# demeter_v28-TSSOP.net
KiCad netlist of a schematic drawn in EAGLE
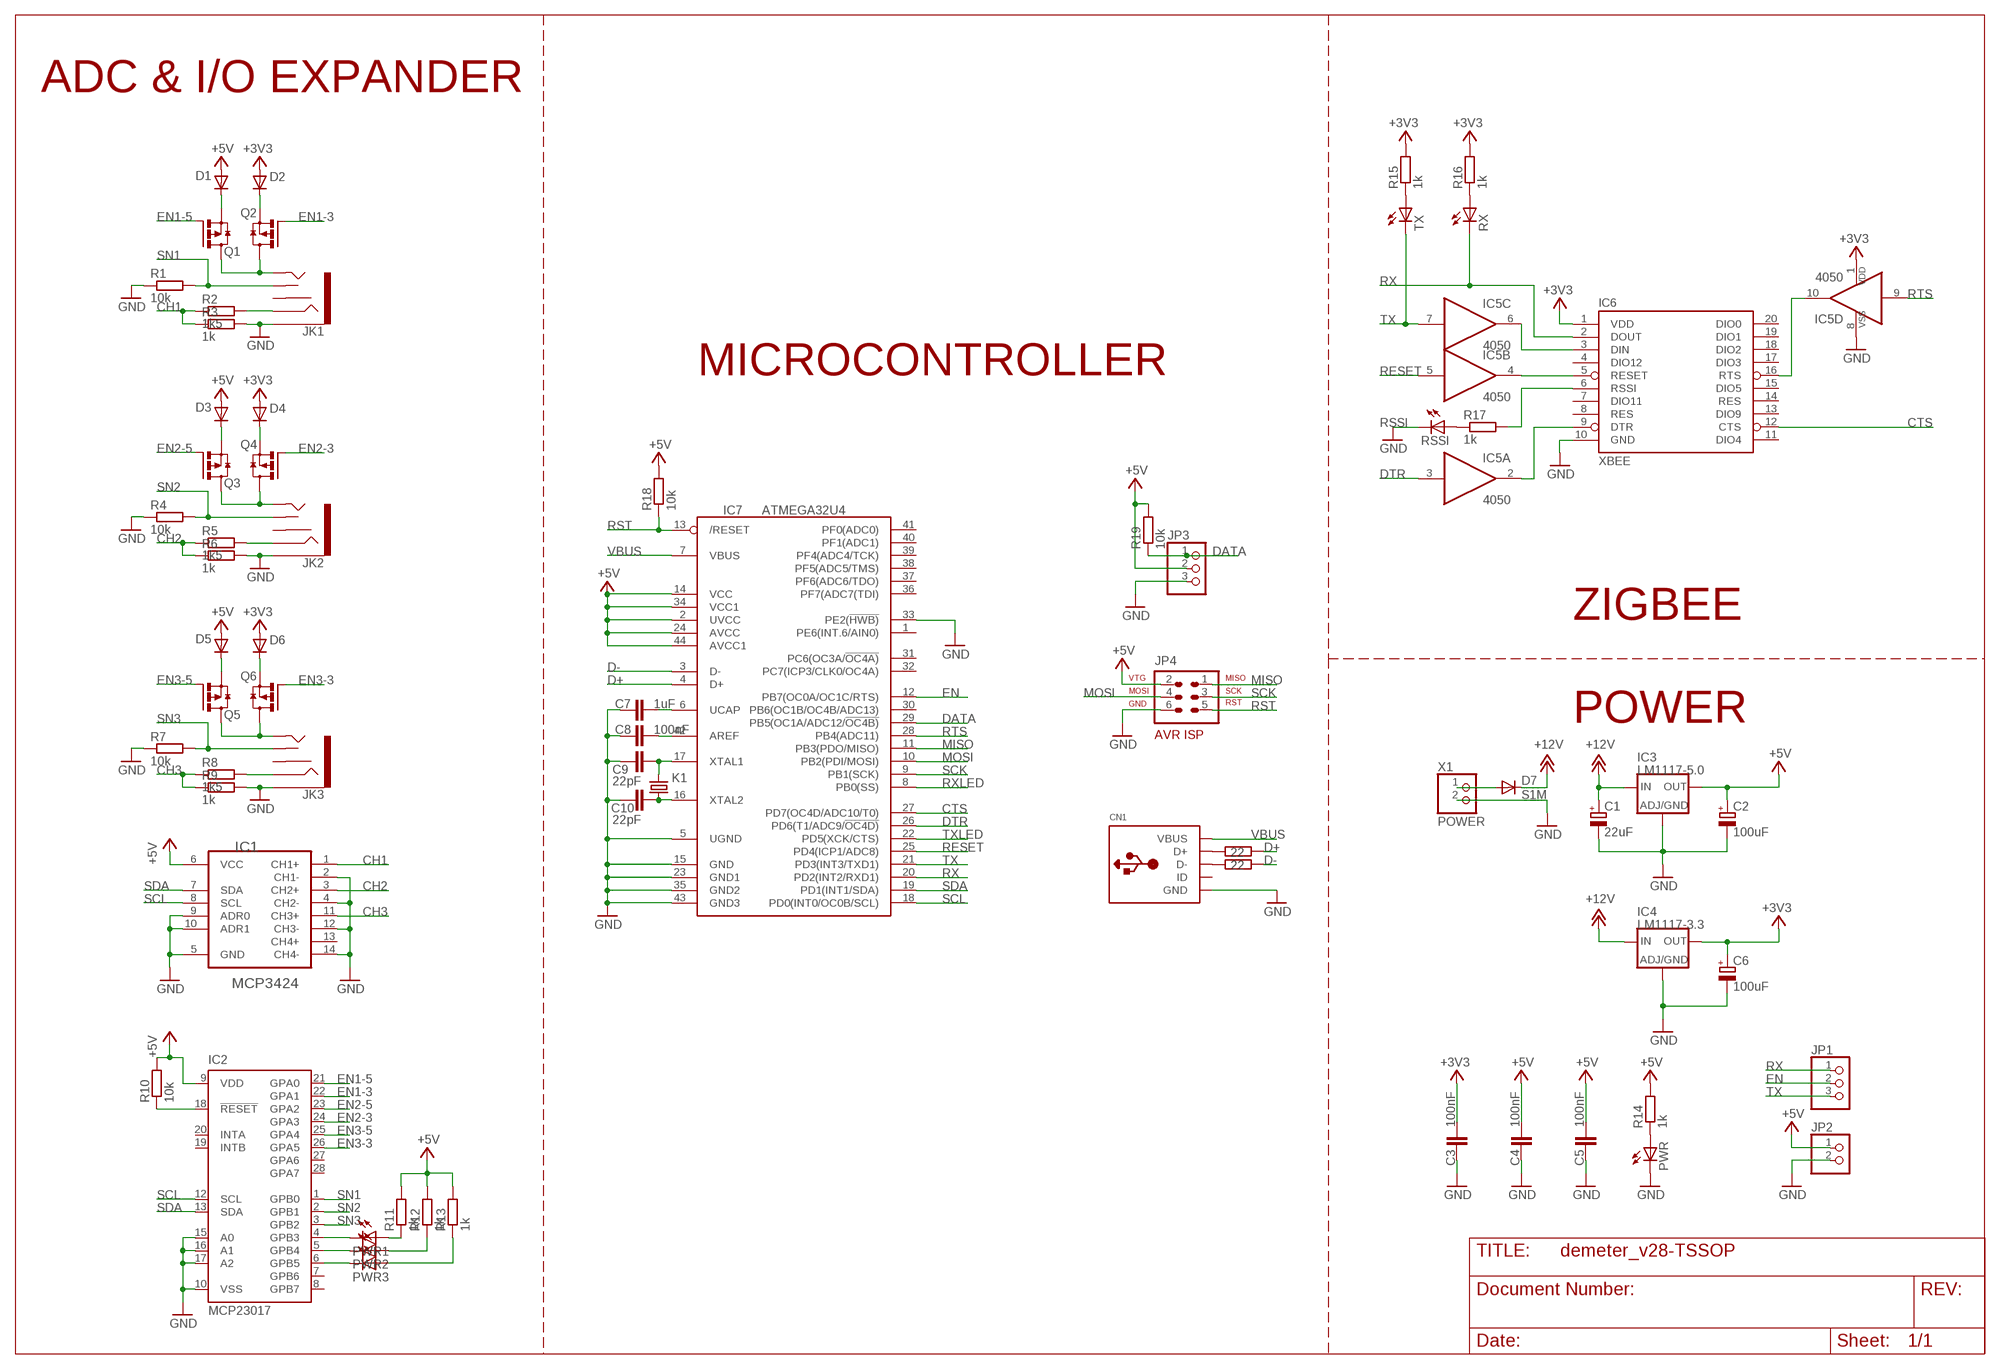
[diagram p0: schematic, sheet 1]

(export (version "E")
  (design (tool "Eeschema 10.0.6"))
  (components
    (comp (ref "C1")
      (value "22uF")
      (footprint "eagle-import:PANASONIC_D")
      (libsource (lib "eagle-import") (part "CPOL-EUPD"))
    )
    (comp (ref "C2")
      (value "100uF")
      (footprint "eagle-import:PANASONIC_D")
      (libsource (lib "eagle-import") (part "CPOL-EUPD"))
    )
    (comp (ref "C3")
      (value "100nF")
      (footprint "eagle-import:C0805K")
      (libsource (lib "eagle-import") (part "C-EUC0805K"))
    )
    (comp (ref "C4")
      (value "100nF")
      (footprint "eagle-import:C0805K")
      (libsource (lib "eagle-import") (part "C-EUC0805K"))
    )
    (comp (ref "C5")
      (value "100nF")
      (footprint "eagle-import:C0805K")
      (libsource (lib "eagle-import") (part "C-EUC0805K"))
    )
    (comp (ref "C6")
      (value "100uF")
      (footprint "eagle-import:PANASONIC_D")
      (libsource (lib "eagle-import") (part "CPOL-EUPD"))
    )
    (comp (ref "C7")
      (value "1uF")
      (footprint "eagle-import:C0805K")
      (libsource (lib "eagle-import") (part "C-EUC0805K"))
    )
    (comp (ref "C8")
      (value "100nF")
      (footprint "eagle-import:C0805K")
      (libsource (lib "eagle-import") (part "C-EUC0805K"))
    )
    (comp (ref "C9")
      (value "22pF")
      (footprint "eagle-import:C0805K")
      (libsource (lib "eagle-import") (part "C-EUC0805K"))
    )
    (comp (ref "C10")
      (value "22pF")
      (footprint "eagle-import:C0805K")
      (libsource (lib "eagle-import") (part "C-EUC0805K"))
    )
    (comp (ref "CN1")
      (value "USBMINIB")
      (footprint "eagle-import:USB-MINIB")
      (libsource (lib "eagle-import") (part "USBMINIB"))
    )
    (comp (ref "D1")
      (value "MBR0520")
      (footprint "eagle-import:SOD123")
      (libsource (lib "eagle-import") (part "MBR0520"))
    )
    (comp (ref "D2")
      (value "MBR0520")
      (footprint "eagle-import:SOD123")
      (libsource (lib "eagle-import") (part "MBR0520"))
    )
    (comp (ref "D3")
      (value "MBR0520")
      (footprint "eagle-import:SOD123")
      (libsource (lib "eagle-import") (part "MBR0520"))
    )
    (comp (ref "D4")
      (value "MBR0520")
      (footprint "eagle-import:SOD123")
      (libsource (lib "eagle-import") (part "MBR0520"))
    )
    (comp (ref "D5")
      (value "MBR0520")
      (footprint "eagle-import:SOD123")
      (libsource (lib "eagle-import") (part "MBR0520"))
    )
    (comp (ref "D6")
      (value "MBR0520")
      (footprint "eagle-import:SOD123")
      (libsource (lib "eagle-import") (part "MBR0520"))
    )
    (comp (ref "D7")
      (value "S1M")
      (footprint "eagle-import:DO-214AC")
      (libsource (lib "eagle-import") (part "S1M"))
    )
    (comp (ref "IC1")
      (value "MCP3424")
      (footprint "eagle-import:TSSOP14")
      (libsource (lib "eagle-import") (part "MCP3424T"))
    )
    (comp (ref "IC2")
      (value "MCP23017")
      (footprint "eagle-import:SO28W")
      (fields (field (name "MF") "MICROCHIP") (field (name "MPN") "MCP23017-E/SO"))
      (libsource (lib "eagle-import") (part "MCP23017SO"))
    )
    (comp (ref "IC3")
      (value "LM1117-5.0")
      (footprint "eagle-import:DPACK")
      (libsource (lib "eagle-import") (part "LM1117DT"))
    )
    (comp (ref "IC4")
      (value "LM1117-3.3")
      (footprint "eagle-import:DPACK")
      (libsource (lib "eagle-import") (part "LM1117DT"))
    )
    (comp (ref "IC5")
      (value "4050")
      (footprint "eagle-import:SO16")
      (libsource (lib "eagle-import") (part "4050D"))
    )
    (comp (ref "IC6")
      (value "XBEE")
      (footprint "eagle-import:XBEE-1")
      (libsource (lib "eagle-import") (part "XBEE-1B1"))
    )
    (comp (ref "IC7")
      (value "ATMEGA32U4")
      (footprint "eagle-import:TQFP44")
      (libsource (lib "eagle-import") (part "ATMEGA32U4-AU"))
    )
    (comp (ref "JK1")
      (value "AUDIO-JACK2PTH")
      (footprint "eagle-import:AUDIO-JACK")
      (libsource (lib "eagle-import") (part "AUDIO-JACK2PTH"))
    )
    (comp (ref "JK2")
      (value "AUDIO-JACK2PTH")
      (footprint "eagle-import:AUDIO-JACK")
      (libsource (lib "eagle-import") (part "AUDIO-JACK2PTH"))
    )
    (comp (ref "JK3")
      (value "AUDIO-JACK2PTH")
      (footprint "eagle-import:AUDIO-JACK")
      (libsource (lib "eagle-import") (part "AUDIO-JACK2PTH"))
    )
    (comp (ref "JP1")
      (value "PINHD-1X3180")
      (footprint "eagle-import:1X03")
      (libsource (lib "eagle-import") (part "PINHD-1X3180"))
    )
    (comp (ref "JP2")
      (value "PINHD-1X2")
      (footprint "eagle-import:1X02")
      (libsource (lib "eagle-import") (part "PINHD-1X2"))
    )
    (comp (ref "JP3")
      (value "PINHD-1X3180")
      (footprint "eagle-import:1X03")
      (libsource (lib "eagle-import") (part "PINHD-1X3180"))
    )
    (comp (ref "JP4")
      (value "AVR-ISP")
      (footprint "eagle-import:AVR-ISP-6")
      (libsource (lib "eagle-import") (part "AVR-ISP-6"))
    )
    (comp (ref "K1")
      (value "CRYSTALHC49UP")
      (footprint "eagle-import:HC49UP")
      (libsource (lib "eagle-import") (part "CRYSTALHC49UP"))
    )
    (comp (ref "PWR")
      (value "LED0805")
      (footprint "eagle-import:CHIP-LED0805")
      (libsource (lib "eagle-import") (part "LED0805"))
    )
    (comp (ref "PWR1")
      (value "LED0805")
      (footprint "eagle-import:CHIP-LED0805")
      (libsource (lib "eagle-import") (part "LED0805"))
    )
    (comp (ref "PWR2")
      (value "LED0805")
      (footprint "eagle-import:CHIP-LED0805")
      (libsource (lib "eagle-import") (part "LED0805"))
    )
    (comp (ref "PWR3")
      (value "LED0805")
      (footprint "eagle-import:CHIP-LED0805")
      (libsource (lib "eagle-import") (part "LED0805"))
    )
    (comp (ref "Q1")
      (value "IRLML6402")
      (footprint "eagle-import:SOT23")
      (libsource (lib "eagle-import") (part "IRLML6402"))
    )
    (comp (ref "Q2")
      (value "IRLML6402")
      (footprint "eagle-import:SOT23")
      (libsource (lib "eagle-import") (part "IRLML6402"))
    )
    (comp (ref "Q3")
      (value "IRLML6402")
      (footprint "eagle-import:SOT23")
      (libsource (lib "eagle-import") (part "IRLML6402"))
    )
    (comp (ref "Q4")
      (value "IRLML6402")
      (footprint "eagle-import:SOT23")
      (libsource (lib "eagle-import") (part "IRLML6402"))
    )
    (comp (ref "Q5")
      (value "IRLML6402")
      (footprint "eagle-import:SOT23")
      (libsource (lib "eagle-import") (part "IRLML6402"))
    )
    (comp (ref "Q6")
      (value "IRLML6402")
      (footprint "eagle-import:SOT23")
      (libsource (lib "eagle-import") (part "IRLML6402"))
    )
    (comp (ref "R1")
      (value "10k")
      (footprint "eagle-import:R0805")
      (libsource (lib "eagle-import") (part "R-EU_R0805"))
    )
    (comp (ref "R2")
      (value "1k5")
      (footprint "eagle-import:R0805")
      (libsource (lib "eagle-import") (part "R-EU_R0805"))
    )
    (comp (ref "R3")
      (value "1k")
      (footprint "eagle-import:R0805")
      (libsource (lib "eagle-import") (part "R-EU_R0805"))
    )
    (comp (ref "R4")
      (value "10k")
      (footprint "eagle-import:R0805")
      (libsource (lib "eagle-import") (part "R-EU_R0805"))
    )
    (comp (ref "R5")
      (value "1k5")
      (footprint "eagle-import:R0805")
      (libsource (lib "eagle-import") (part "R-EU_R0805"))
    )
    (comp (ref "R6")
      (value "1k")
      (footprint "eagle-import:R0805")
      (libsource (lib "eagle-import") (part "R-EU_R0805"))
    )
    (comp (ref "R7")
      (value "10k")
      (footprint "eagle-import:R0805")
      (libsource (lib "eagle-import") (part "R-EU_R0805"))
    )
    (comp (ref "R8")
      (value "1k5")
      (footprint "eagle-import:R0805")
      (libsource (lib "eagle-import") (part "R-EU_R0805"))
    )
    (comp (ref "R9")
      (value "1k")
      (footprint "eagle-import:R0805")
      (libsource (lib "eagle-import") (part "R-EU_R0805"))
    )
    (comp (ref "R10")
      (value "10k")
      (footprint "eagle-import:R0805")
      (libsource (lib "eagle-import") (part "R-EU_R0805"))
    )
    (comp (ref "R11")
      (value "1k")
      (footprint "eagle-import:R0805")
      (libsource (lib "eagle-import") (part "R-EU_R0805"))
    )
    (comp (ref "R12")
      (value "1k")
      (footprint "eagle-import:R0805")
      (libsource (lib "eagle-import") (part "R-EU_R0805"))
    )
    (comp (ref "R13")
      (value "1k")
      (footprint "eagle-import:R0805")
      (libsource (lib "eagle-import") (part "R-EU_R0805"))
    )
    (comp (ref "R14")
      (value "1k")
      (footprint "eagle-import:R0805")
      (libsource (lib "eagle-import") (part "R-EU_R0805"))
    )
    (comp (ref "R15")
      (value "1k")
      (footprint "eagle-import:R0805")
      (libsource (lib "eagle-import") (part "R-EU_R0805"))
    )
    (comp (ref "R16")
      (value "1k")
      (footprint "eagle-import:R0805")
      (libsource (lib "eagle-import") (part "R-EU_R0805"))
    )
    (comp (ref "R17")
      (value "1k")
      (footprint "eagle-import:R0805")
      (libsource (lib "eagle-import") (part "R-EU_R0805"))
    )
    (comp (ref "R18")
      (value "10k")
      (footprint "eagle-import:R0805")
      (libsource (lib "eagle-import") (part "R-EU_R0805"))
    )
    (comp (ref "R19")
      (value "10k")
      (footprint "eagle-import:R0805")
      (libsource (lib "eagle-import") (part "R-EU_R0805"))
    )
    (comp (ref "R20")
      (value "22")
      (footprint "eagle-import:R0805")
      (libsource (lib "eagle-import") (part "R-EU_R0805"))
    )
    (comp (ref "R21")
      (value "22")
      (footprint "eagle-import:R0805")
      (libsource (lib "eagle-import") (part "R-EU_R0805"))
    )
    (comp (ref "RSSI")
      (value "LED0805")
      (footprint "eagle-import:CHIP-LED0805")
      (libsource (lib "eagle-import") (part "LED0805"))
    )
    (comp (ref "RX")
      (value "LED0805")
      (footprint "eagle-import:CHIP-LED0805")
      (libsource (lib "eagle-import") (part "LED0805"))
    )
    (comp (ref "TX")
      (value "LED0805")
      (footprint "eagle-import:CHIP-LED0805")
      (libsource (lib "eagle-import") (part "LED0805"))
    )
    (comp (ref "X1")
      (value "POWER")
      (footprint "eagle-import:W237-102")
      (libsource (lib "eagle-import") (part "W237-102"))
    )
  )
  (nets
    (net (code "1") (name "+3V3") (class "Default")
      (node (ref "C3") (pin "1") (pinfunction "1_1") (pintype "passive"))
      (node (ref "C6") (pin "+") (pinfunction "+_+") (pintype "passive"))
      (node (ref "D2") (pin "A") (pinfunction "A_A") (pintype "passive"))
      (node (ref "D4") (pin "A") (pinfunction "A_A") (pintype "passive"))
      (node (ref "D6") (pin "A") (pinfunction "A_A") (pintype "passive"))
      (node (ref "IC4") (pin "4") (pinfunction "OUT_4") (pintype "passive"))
      (node (ref "IC5") (pin "1") (pinfunction "VDD_1") (pintype "power_in"))
      (node (ref "IC6") (pin "1") (pinfunction "VDD_1") (pintype "power_in"))
      (node (ref "R15") (pin "2") (pinfunction "2_2") (pintype "passive"))
      (node (ref "R16") (pin "2") (pinfunction "2_2") (pintype "passive"))
    )
    (net (code "2") (name "+5V") (class "Default")
      (node (ref "C2") (pin "+") (pinfunction "+_+") (pintype "passive"))
      (node (ref "C4") (pin "1") (pinfunction "1_1") (pintype "passive"))
      (node (ref "C5") (pin "1") (pinfunction "1_1") (pintype "passive"))
      (node (ref "D1") (pin "A") (pinfunction "A_A") (pintype "passive"))
      (node (ref "D3") (pin "A") (pinfunction "A_A") (pintype "passive"))
      (node (ref "D5") (pin "A") (pinfunction "A_A") (pintype "passive"))
      (node (ref "IC1") (pin "6") (pinfunction "VCC_6") (pintype "power_in"))
      (node (ref "IC2") (pin "9") (pinfunction "VDD_9") (pintype "power_in"))
      (node (ref "IC3") (pin "4") (pinfunction "OUT_4") (pintype "passive"))
      (node (ref "IC7") (pin "14") (pinfunction "VCC_14") (pintype "bidirectional"))
      (node (ref "IC7") (pin "2") (pinfunction "UVCC_2") (pintype "bidirectional"))
      (node (ref "IC7") (pin "24") (pinfunction "AVCC_24") (pintype "bidirectional"))
      (node (ref "IC7") (pin "34") (pinfunction "VCC1_34") (pintype "bidirectional"))
      (node (ref "IC7") (pin "44") (pinfunction "AVCC1_44") (pintype "bidirectional"))
      (node (ref "JP2") (pin "1") (pinfunction "1_1") (pintype "passive"))
      (node (ref "JP3") (pin "2") (pinfunction "2_2") (pintype "passive"))
      (node (ref "JP4") (pin "2") (pinfunction "VTG_2") (pintype "passive"))
      (node (ref "R10") (pin "2") (pinfunction "2_2") (pintype "passive"))
      (node (ref "R11") (pin "2") (pinfunction "2_2") (pintype "passive"))
      (node (ref "R12") (pin "2") (pinfunction "2_2") (pintype "passive"))
      (node (ref "R13") (pin "2") (pinfunction "2_2") (pintype "passive"))
      (node (ref "R14") (pin "2") (pinfunction "2_2") (pintype "passive"))
      (node (ref "R18") (pin "2") (pinfunction "2_2") (pintype "passive"))
      (node (ref "R19") (pin "2") (pinfunction "2_2") (pintype "passive"))
    )
    (net (code "3") (name "+12V") (class "Default")
      (node (ref "C1") (pin "+") (pinfunction "+_+") (pintype "passive"))
      (node (ref "D7") (pin "C") (pinfunction "C_C") (pintype "passive"))
      (node (ref "IC3") (pin "3") (pinfunction "IN_3") (pintype "input"))
      (node (ref "IC4") (pin "3") (pinfunction "IN_3") (pintype "input"))
    )
    (net (code "4") (name "/CH1") (class "Default")
      (node (ref "IC1") (pin "1") (pinfunction "CH1+_1") (pintype "input"))
      (node (ref "R2") (pin "1") (pinfunction "1_1") (pintype "passive"))
      (node (ref "R3") (pin "1") (pinfunction "1_1") (pintype "passive"))
    )
    (net (code "5") (name "/CH2") (class "Default")
      (node (ref "IC1") (pin "3") (pinfunction "CH2+_3") (pintype "input"))
      (node (ref "R5") (pin "1") (pinfunction "1_1") (pintype "passive"))
      (node (ref "R6") (pin "1") (pinfunction "1_1") (pintype "passive"))
    )
    (net (code "6") (name "/CH3") (class "Default")
      (node (ref "IC1") (pin "11") (pinfunction "CH3+_11") (pintype "input"))
      (node (ref "R8") (pin "1") (pinfunction "1_1") (pintype "passive"))
      (node (ref "R9") (pin "1") (pinfunction "1_1") (pintype "passive"))
    )
    (net (code "7") (name "/CTS") (class "Default")
      (node (ref "IC6") (pin "12") (pinfunction "CTS_12") (pintype "output"))
      (node (ref "IC7") (pin "27") (pinfunction "PD7(OC4D/ADC10/T0)_27") (pintype "bidirectional"))
    )
    (net (code "8") (name "/D+") (class "Default")
      (node (ref "IC7") (pin "4") (pinfunction "D+_4") (pintype "bidirectional"))
      (node (ref "R20") (pin "1") (pinfunction "1_1") (pintype "passive"))
    )
    (net (code "9") (name "/D-") (class "Default")
      (node (ref "IC7") (pin "3") (pinfunction "D-_3") (pintype "bidirectional"))
      (node (ref "R21") (pin "1") (pinfunction "1_1") (pintype "passive"))
    )
    (net (code "10") (name "/DATA") (class "Default")
      (node (ref "IC7") (pin "29") (pinfunction "PB5(OC1A/ADC12/~{OC4B})_29") (pintype "bidirectional"))
      (node (ref "JP3") (pin "1") (pinfunction "1_1") (pintype "passive"))
      (node (ref "R19") (pin "1") (pinfunction "1_1") (pintype "passive"))
    )
    (net (code "11") (name "/DTR") (class "Default")
      (node (ref "IC5") (pin "3") (pinfunction "I_3") (pintype "input"))
      (node (ref "IC7") (pin "26") (pinfunction "PD6(T1/ADC9/~{OC4D})_26") (pintype "bidirectional"))
    )
    (net (code "12") (name "/EN") (class "Default")
      (node (ref "IC7") (pin "12") (pinfunction "PB7(OC0A/OC1C/RTS)_12") (pintype "bidirectional"))
      (node (ref "JP1") (pin "2") (pinfunction "2_2") (pintype "passive"))
    )
    (net (code "13") (name "/EN1-3") (class "Default")
      (node (ref "IC2") (pin "22") (pinfunction "GPA1_22") (pintype "bidirectional"))
      (node (ref "Q2") (pin "1") (pinfunction "G_1") (pintype "passive"))
    )
    (net (code "14") (name "/EN1-5") (class "Default")
      (node (ref "IC2") (pin "21") (pinfunction "GPA0_21") (pintype "bidirectional"))
      (node (ref "Q1") (pin "1") (pinfunction "G_1") (pintype "passive"))
    )
    (net (code "15") (name "/EN2-3") (class "Default")
      (node (ref "IC2") (pin "24") (pinfunction "GPA3_24") (pintype "bidirectional"))
      (node (ref "Q4") (pin "1") (pinfunction "G_1") (pintype "passive"))
    )
    (net (code "16") (name "/EN2-5") (class "Default")
      (node (ref "IC2") (pin "23") (pinfunction "GPA2_23") (pintype "bidirectional"))
      (node (ref "Q3") (pin "1") (pinfunction "G_1") (pintype "passive"))
    )
    (net (code "17") (name "/EN3-3") (class "Default")
      (node (ref "IC2") (pin "26") (pinfunction "GPA5_26") (pintype "bidirectional"))
      (node (ref "Q6") (pin "1") (pinfunction "G_1") (pintype "passive"))
    )
    (net (code "18") (name "/EN3-5") (class "Default")
      (node (ref "IC2") (pin "25") (pinfunction "GPA4_25") (pintype "bidirectional"))
      (node (ref "Q5") (pin "1") (pinfunction "G_1") (pintype "passive"))
    )
    (net (code "19") (name "/MISO") (class "Default")
      (node (ref "IC7") (pin "11") (pinfunction "PB3(PDO/MISO)_11") (pintype "bidirectional"))
      (node (ref "JP4") (pin "1") (pinfunction "MISO_1") (pintype "passive"))
    )
    (net (code "20") (name "/MOSI") (class "Default")
      (node (ref "IC7") (pin "10") (pinfunction "PB2(PDI/MOSI)_10") (pintype "bidirectional"))
      (node (ref "JP4") (pin "4") (pinfunction "MOSI_4") (pintype "passive"))
    )
    (net (code "21") (name "/RESET") (class "Default")
      (node (ref "IC5") (pin "5") (pinfunction "I_5") (pintype "input"))
      (node (ref "IC7") (pin "25") (pinfunction "PD4(ICP1/ADC8)_25") (pintype "bidirectional"))
    )
    (net (code "22") (name "/RSSI") (class "Default")
      (node (ref "IC6") (pin "6") (pinfunction "RSSI_6") (pintype "bidirectional"))
      (node (ref "R17") (pin "2") (pinfunction "2_2") (pintype "passive"))
    )
    (net (code "23") (name "/RST") (class "Default")
      (node (ref "IC7") (pin "13") (pinfunction "/RESET_13") (pintype "bidirectional"))
      (node (ref "JP4") (pin "5") (pinfunction "RST_5") (pintype "passive"))
      (node (ref "R18") (pin "1") (pinfunction "1_1") (pintype "passive"))
    )
    (net (code "24") (name "/RTS") (class "Default")
      (node (ref "IC5") (pin "9") (pinfunction "I_9") (pintype "input"))
      (node (ref "IC7") (pin "28") (pinfunction "PB4(ADC11)_28") (pintype "bidirectional"))
    )
    (net (code "25") (name "/RX") (class "Default")
      (node (ref "IC6") (pin "2") (pinfunction "DOUT_2") (pintype "output"))
      (node (ref "IC7") (pin "20") (pinfunction "PD2(INT2/RXD1)_20") (pintype "bidirectional"))
      (node (ref "JP1") (pin "1") (pinfunction "1_1") (pintype "passive"))
      (node (ref "RX") (pin "C") (pinfunction "C_C") (pintype "passive"))
    )
    (net (code "26") (name "/RXLED") (class "Default")
      (node (ref "IC7") (pin "8") (pinfunction "PB0(SS)_8") (pintype "bidirectional"))
    )
    (net (code "27") (name "/SCK") (class "Default")
      (node (ref "IC7") (pin "9") (pinfunction "PB1(SCK)_9") (pintype "bidirectional"))
      (node (ref "JP4") (pin "3") (pinfunction "SCK_3") (pintype "passive"))
    )
    (net (code "28") (name "/SCL") (class "Default")
      (node (ref "IC1") (pin "8") (pinfunction "SCL_8") (pintype "input"))
      (node (ref "IC2") (pin "12") (pinfunction "SCL_12") (pintype "input"))
      (node (ref "IC7") (pin "18") (pinfunction "PD0(INT0/OC0B/SCL)_18") (pintype "bidirectional"))
    )
    (net (code "29") (name "/SDA") (class "Default")
      (node (ref "IC1") (pin "7") (pinfunction "SDA_7") (pintype "bidirectional"))
      (node (ref "IC2") (pin "13") (pinfunction "SDA_13") (pintype "bidirectional"))
      (node (ref "IC7") (pin "19") (pinfunction "PD1(INT1/SDA)_19") (pintype "bidirectional"))
    )
    (net (code "30") (name "/SN1") (class "Default")
      (node (ref "IC2") (pin "1") (pinfunction "GPB0_1") (pintype "bidirectional"))
      (node (ref "JK1") (pin "TSH") (pinfunction "TSH_TSH") (pintype "bidirectional"))
      (node (ref "R1") (pin "2") (pinfunction "2_2") (pintype "passive"))
    )
    (net (code "31") (name "/SN2") (class "Default")
      (node (ref "IC2") (pin "2") (pinfunction "GPB1_2") (pintype "bidirectional"))
      (node (ref "JK2") (pin "TSH") (pinfunction "TSH_TSH") (pintype "bidirectional"))
      (node (ref "R4") (pin "2") (pinfunction "2_2") (pintype "passive"))
    )
    (net (code "32") (name "/SN3") (class "Default")
      (node (ref "IC2") (pin "3") (pinfunction "GPB2_3") (pintype "bidirectional"))
      (node (ref "JK3") (pin "TSH") (pinfunction "TSH_TSH") (pintype "bidirectional"))
      (node (ref "R7") (pin "2") (pinfunction "2_2") (pintype "passive"))
    )
    (net (code "33") (name "/TX") (class "Default")
      (node (ref "IC5") (pin "7") (pinfunction "I_7") (pintype "input"))
      (node (ref "IC7") (pin "21") (pinfunction "PD3(INT3/TXD1)_21") (pintype "bidirectional"))
      (node (ref "JP1") (pin "3") (pinfunction "3_3") (pintype "passive"))
      (node (ref "TX") (pin "C") (pinfunction "C_C") (pintype "passive"))
    )
    (net (code "34") (name "/TXLED") (class "Default")
      (node (ref "IC7") (pin "22") (pinfunction "PD5(XCK/CTS)_22") (pintype "bidirectional"))
    )
    (net (code "35") (name "/VBUS") (class "Default")
      (node (ref "CN1") (pin "VBUS") (pinfunction "VBUS_VBUS") (pintype "power_in"))
      (node (ref "IC7") (pin "7") (pinfunction "VBUS_7") (pintype "bidirectional"))
    )
    (net (code "36") (name "GND") (class "Default")
      (node (ref "C1") (pin "-") (pinfunction "-_-") (pintype "passive"))
      (node (ref "C10") (pin "2") (pinfunction "2_2") (pintype "passive"))
      (node (ref "C2") (pin "-") (pinfunction "-_-") (pintype "passive"))
      (node (ref "C3") (pin "2") (pinfunction "2_2") (pintype "passive"))
      (node (ref "C4") (pin "2") (pinfunction "2_2") (pintype "passive"))
      (node (ref "C5") (pin "2") (pinfunction "2_2") (pintype "passive"))
      (node (ref "C6") (pin "-") (pinfunction "-_-") (pintype "passive"))
      (node (ref "C7") (pin "2") (pinfunction "2_2") (pintype "passive"))
      (node (ref "C8") (pin "2") (pinfunction "2_2") (pintype "passive"))
      (node (ref "C9") (pin "2") (pinfunction "2_2") (pintype "passive"))
      (node (ref "CN1") (pin "GND") (pinfunction "GND_GND") (pintype "power_in"))
      (node (ref "CN1") (pin "GND1") (pinfunction "GND_GND1") (pintype "power_in"))
      (node (ref "CN1") (pin "GND2") (pinfunction "GND_GND2") (pintype "power_in"))
      (node (ref "CN1") (pin "GND3") (pinfunction "GND_GND3") (pintype "power_in"))
      (node (ref "CN1") (pin "GND4") (pinfunction "GND_GND4") (pintype "power_in"))
      (node (ref "IC1") (pin "10") (pinfunction "ADR1_10") (pintype "input"))
      (node (ref "IC1") (pin "12") (pinfunction "CH3-_12") (pintype "input"))
      (node (ref "IC1") (pin "14") (pinfunction "CH4-_14") (pintype "input"))
      (node (ref "IC1") (pin "2") (pinfunction "CH1-_2") (pintype "input"))
      (node (ref "IC1") (pin "4") (pinfunction "CH2-_4") (pintype "input"))
      (node (ref "IC1") (pin "5") (pinfunction "GND_5") (pintype "power_in"))
      (node (ref "IC1") (pin "9") (pinfunction "ADR0_9") (pintype "input"))
      (node (ref "IC2") (pin "10") (pinfunction "VSS_10") (pintype "power_in"))
      (node (ref "IC2") (pin "15") (pinfunction "A0_15") (pintype "input"))
      (node (ref "IC2") (pin "16") (pinfunction "A1_16") (pintype "input"))
      (node (ref "IC2") (pin "17") (pinfunction "A2_17") (pintype "input"))
      (node (ref "IC3") (pin "1") (pinfunction "ADJ_1") (pintype "input"))
      (node (ref "IC4") (pin "1") (pinfunction "ADJ_1") (pintype "input"))
      (node (ref "IC5") (pin "8") (pinfunction "VSS_8") (pintype "power_in"))
      (node (ref "IC6") (pin "10") (pinfunction "GND_10") (pintype "power_in"))
      (node (ref "IC7") (pin "15") (pinfunction "GND_15") (pintype "bidirectional"))
      (node (ref "IC7") (pin "23") (pinfunction "GND1_23") (pintype "bidirectional"))
      (node (ref "IC7") (pin "33") (pinfunction "PE2(~{HWB})_33") (pintype "bidirectional"))
      (node (ref "IC7") (pin "35") (pinfunction "GND2_35") (pintype "bidirectional"))
      (node (ref "IC7") (pin "43") (pinfunction "GND3_43") (pintype "bidirectional"))
      (node (ref "IC7") (pin "5") (pinfunction "UGND_5") (pintype "bidirectional"))
      (node (ref "JK1") (pin "SLEEVE") (pinfunction "SLEEVE_SLEEVE") (pintype "bidirectional"))
      (node (ref "JK2") (pin "SLEEVE") (pinfunction "SLEEVE_SLEEVE") (pintype "bidirectional"))
      (node (ref "JK3") (pin "SLEEVE") (pinfunction "SLEEVE_SLEEVE") (pintype "bidirectional"))
      (node (ref "JP2") (pin "2") (pinfunction "2_2") (pintype "passive"))
      (node (ref "JP3") (pin "3") (pinfunction "3_3") (pintype "passive"))
      (node (ref "JP4") (pin "6") (pinfunction "GND_6") (pintype "passive"))
      (node (ref "PWR") (pin "C") (pinfunction "C_C") (pintype "passive"))
      (node (ref "R1") (pin "1") (pinfunction "1_1") (pintype "passive"))
      (node (ref "R3") (pin "2") (pinfunction "2_2") (pintype "passive"))
      (node (ref "R4") (pin "1") (pinfunction "1_1") (pintype "passive"))
      (node (ref "R6") (pin "2") (pinfunction "2_2") (pintype "passive"))
      (node (ref "R7") (pin "1") (pinfunction "1_1") (pintype "passive"))
      (node (ref "R9") (pin "2") (pinfunction "2_2") (pintype "passive"))
      (node (ref "RSSI") (pin "C") (pinfunction "C_C") (pintype "passive"))
      (node (ref "X1") (pin "2") (pinfunction "2_2") (pintype "passive"))
    )
    (net (code "37") (name "Net-(CN1-PadD+)") (class "Default")
      (node (ref "CN1") (pin "D+") (pinfunction "D+_D+") (pintype "bidirectional"))
      (node (ref "R20") (pin "2") (pinfunction "2_2") (pintype "passive"))
    )
    (net (code "38") (name "Net-(CN1-PadD-)") (class "Default")
      (node (ref "CN1") (pin "D-") (pinfunction "D-_D-") (pintype "bidirectional"))
      (node (ref "R21") (pin "2") (pinfunction "2_2") (pintype "passive"))
    )
    (net (code "39") (name "Net-(D7-PadA)") (class "Default")
      (node (ref "D7") (pin "A") (pinfunction "A_A") (pintype "passive"))
      (node (ref "X1") (pin "1") (pinfunction "1_1") (pintype "passive"))
    )
    (net (code "40") (name "Net-(IC2-GPB3)") (class "Default")
      (node (ref "IC2") (pin "4") (pinfunction "GPB3_4") (pintype "bidirectional"))
      (node (ref "PWR1") (pin "C") (pinfunction "C_C") (pintype "passive"))
    )
    (net (code "41") (name "Net-(IC2-GPB4)") (class "Default")
      (node (ref "IC2") (pin "5") (pinfunction "GPB4_5") (pintype "bidirectional"))
      (node (ref "PWR2") (pin "C") (pinfunction "C_C") (pintype "passive"))
    )
    (net (code "42") (name "Net-(IC2-GPB5)") (class "Default")
      (node (ref "IC2") (pin "6") (pinfunction "GPB5_6") (pintype "bidirectional"))
      (node (ref "PWR3") (pin "C") (pinfunction "C_C") (pintype "passive"))
    )
    (net (code "43") (name "Net-(IC2-~{RESET})") (class "Default")
      (node (ref "IC2") (pin "18") (pinfunction "~{RESET}_18") (pintype "input"))
      (node (ref "R10") (pin "1") (pinfunction "1_1") (pintype "passive"))
    )
    (net (code "44") (name "Net-(IC5A-O)") (class "Default")
      (node (ref "IC5") (pin "2") (pinfunction "O_2") (pintype "output"))
      (node (ref "IC6") (pin "9") (pinfunction "DTR_9") (pintype "bidirectional"))
    )
    (net (code "45") (name "Net-(IC5B-O)") (class "Default")
      (node (ref "IC5") (pin "4") (pinfunction "O_4") (pintype "output"))
      (node (ref "IC6") (pin "5") (pinfunction "RESET_5") (pintype "input"))
    )
    (net (code "46") (name "Net-(IC5C-O)") (class "Default")
      (node (ref "IC5") (pin "6") (pinfunction "O_6") (pintype "output"))
      (node (ref "IC6") (pin "3") (pinfunction "DIN_3") (pintype "input"))
    )
    (net (code "47") (name "Net-(IC5D-O)") (class "Default")
      (node (ref "IC5") (pin "10") (pinfunction "O_10") (pintype "output"))
      (node (ref "IC6") (pin "16") (pinfunction "RTS_16") (pintype "input"))
    )
    (net (code "48") (name "Net-(IC7-AREF)") (class "Default")
      (node (ref "C8") (pin "1") (pinfunction "1_1") (pintype "passive"))
      (node (ref "IC7") (pin "42") (pinfunction "AREF_42") (pintype "bidirectional"))
    )
    (net (code "49") (name "Net-(IC7-UCAP)") (class "Default")
      (node (ref "C7") (pin "1") (pinfunction "1_1") (pintype "passive"))
      (node (ref "IC7") (pin "6") (pinfunction "UCAP_6") (pintype "bidirectional"))
    )
    (net (code "50") (name "Net-(IC7-XTAL1)") (class "Default")
      (node (ref "C9") (pin "1") (pinfunction "1_1") (pintype "passive"))
      (node (ref "IC7") (pin "17") (pinfunction "XTAL1_17") (pintype "bidirectional"))
      (node (ref "K1") (pin "2") (pinfunction "2_2") (pintype "passive"))
    )
    (net (code "51") (name "Net-(IC7-XTAL2)") (class "Default")
      (node (ref "C10") (pin "1") (pinfunction "1_1") (pintype "passive"))
      (node (ref "IC7") (pin "16") (pinfunction "XTAL2_16") (pintype "bidirectional"))
      (node (ref "K1") (pin "1") (pinfunction "1_1") (pintype "passive"))
    )
    (net (code "52") (name "Net-(JK1-PadRING)") (class "Default")
      (node (ref "JK1") (pin "RING") (pinfunction "RING_RING") (pintype "bidirectional"))
      (node (ref "R2") (pin "2") (pinfunction "2_2") (pintype "passive"))
    )
    (net (code "53") (name "Net-(JK2-PadRING)") (class "Default")
      (node (ref "JK2") (pin "RING") (pinfunction "RING_RING") (pintype "bidirectional"))
      (node (ref "R5") (pin "2") (pinfunction "2_2") (pintype "passive"))
    )
    (net (code "54") (name "Net-(JK3-PadRING)") (class "Default")
      (node (ref "JK3") (pin "RING") (pinfunction "RING_RING") (pintype "bidirectional"))
      (node (ref "R8") (pin "2") (pinfunction "2_2") (pintype "passive"))
    )
    (net (code "55") (name "Net-(PWR-PadA)") (class "Default")
      (node (ref "PWR") (pin "A") (pinfunction "A_A") (pintype "passive"))
      (node (ref "R14") (pin "1") (pinfunction "1_1") (pintype "passive"))
    )
    (net (code "56") (name "Net-(PWR1-PadA)") (class "Default")
      (node (ref "PWR1") (pin "A") (pinfunction "A_A") (pintype "passive"))
      (node (ref "R11") (pin "1") (pinfunction "1_1") (pintype "passive"))
    )
    (net (code "57") (name "Net-(PWR2-PadA)") (class "Default")
      (node (ref "PWR2") (pin "A") (pinfunction "A_A") (pintype "passive"))
      (node (ref "R12") (pin "1") (pinfunction "1_1") (pintype "passive"))
    )
    (net (code "58") (name "Net-(PWR3-PadA)") (class "Default")
      (node (ref "PWR3") (pin "A") (pinfunction "A_A") (pintype "passive"))
      (node (ref "R13") (pin "1") (pinfunction "1_1") (pintype "passive"))
    )
    (net (code "59") (name "Net-(Q1-D)") (class "Default")
      (node (ref "JK1") (pin "TIP") (pinfunction "TIP_TIP") (pintype "bidirectional"))
      (node (ref "Q1") (pin "3") (pinfunction "D_3") (pintype "passive"))
      (node (ref "Q2") (pin "3") (pinfunction "D_3") (pintype "passive"))
    )
    (net (code "60") (name "Net-(Q1-S)") (class "Default")
      (node (ref "D1") (pin "C") (pinfunction "C_C") (pintype "passive"))
      (node (ref "Q1") (pin "2") (pinfunction "S_2") (pintype "passive"))
    )
    (net (code "61") (name "Net-(Q2-S)") (class "Default")
      (node (ref "D2") (pin "C") (pinfunction "C_C") (pintype "passive"))
      (node (ref "Q2") (pin "2") (pinfunction "S_2") (pintype "passive"))
    )
    (net (code "62") (name "Net-(Q3-D)") (class "Default")
      (node (ref "JK2") (pin "TIP") (pinfunction "TIP_TIP") (pintype "bidirectional"))
      (node (ref "Q3") (pin "3") (pinfunction "D_3") (pintype "passive"))
      (node (ref "Q4") (pin "3") (pinfunction "D_3") (pintype "passive"))
    )
    (net (code "63") (name "Net-(Q3-S)") (class "Default")
      (node (ref "D3") (pin "C") (pinfunction "C_C") (pintype "passive"))
      (node (ref "Q3") (pin "2") (pinfunction "S_2") (pintype "passive"))
    )
    (net (code "64") (name "Net-(Q4-S)") (class "Default")
      (node (ref "D4") (pin "C") (pinfunction "C_C") (pintype "passive"))
      (node (ref "Q4") (pin "2") (pinfunction "S_2") (pintype "passive"))
    )
    (net (code "65") (name "Net-(Q5-D)") (class "Default")
      (node (ref "JK3") (pin "TIP") (pinfunction "TIP_TIP") (pintype "bidirectional"))
      (node (ref "Q5") (pin "3") (pinfunction "D_3") (pintype "passive"))
      (node (ref "Q6") (pin "3") (pinfunction "D_3") (pintype "passive"))
    )
    (net (code "66") (name "Net-(Q5-S)") (class "Default")
      (node (ref "D5") (pin "C") (pinfunction "C_C") (pintype "passive"))
      (node (ref "Q5") (pin "2") (pinfunction "S_2") (pintype "passive"))
    )
    (net (code "67") (name "Net-(Q6-S)") (class "Default")
      (node (ref "D6") (pin "C") (pinfunction "C_C") (pintype "passive"))
      (node (ref "Q6") (pin "2") (pinfunction "S_2") (pintype "passive"))
    )
    (net (code "68") (name "Net-(R15-Pad1)") (class "Default")
      (node (ref "R15") (pin "1") (pinfunction "1_1") (pintype "passive"))
      (node (ref "TX") (pin "A") (pinfunction "A_A") (pintype "passive"))
    )
    (net (code "69") (name "Net-(R16-Pad1)") (class "Default")
      (node (ref "R16") (pin "1") (pinfunction "1_1") (pintype "passive"))
      (node (ref "RX") (pin "A") (pinfunction "A_A") (pintype "passive"))
    )
    (net (code "70") (name "Net-(R17-Pad1)") (class "Default")
      (node (ref "R17") (pin "1") (pinfunction "1_1") (pintype "passive"))
      (node (ref "RSSI") (pin "A") (pinfunction "A_A") (pintype "passive"))
    )
    (net (code "71") (name "unconnected-(CN1-PadID)") (class "Default")
      (node (ref "CN1") (pin "ID") (pinfunction "ID_ID") (pintype "bidirectional"))
    )
    (net (code "72") (name "unconnected-(IC1-CH4+-Pad13)") (class "Default")
      (node (ref "IC1") (pin "13") (pinfunction "CH4+_13") (pintype "input"))
    )
    (net (code "73") (name "unconnected-(IC2-GPA6-Pad27)") (class "Default")
      (node (ref "IC2") (pin "27") (pinfunction "GPA6_27") (pintype "bidirectional"))
    )
    (net (code "74") (name "unconnected-(IC2-GPA7-Pad28)") (class "Default")
      (node (ref "IC2") (pin "28") (pinfunction "GPA7_28") (pintype "bidirectional"))
    )
    (net (code "75") (name "unconnected-(IC2-GPB6-Pad7)") (class "Default")
      (node (ref "IC2") (pin "7") (pinfunction "GPB6_7") (pintype "bidirectional"))
    )
    (net (code "76") (name "unconnected-(IC2-GPB7-Pad8)") (class "Default")
      (node (ref "IC2") (pin "8") (pinfunction "GPB7_8") (pintype "bidirectional"))
    )
    (net (code "77") (name "unconnected-(IC2-INTA-Pad20)") (class "Default")
      (node (ref "IC2") (pin "20") (pinfunction "INTA_20") (pintype "output"))
    )
    (net (code "78") (name "unconnected-(IC2-INTB-Pad19)") (class "Default")
      (node (ref "IC2") (pin "19") (pinfunction "INTB_19") (pintype "output"))
    )
    (net (code "79") (name "unconnected-(IC6-DIO0-Pad20)") (class "Default")
      (node (ref "IC6") (pin "20") (pinfunction "DIO0_20") (pintype "bidirectional"))
    )
    (net (code "80") (name "unconnected-(IC6-DIO1-Pad19)") (class "Default")
      (node (ref "IC6") (pin "19") (pinfunction "DIO1_19") (pintype "bidirectional"))
    )
    (net (code "81") (name "unconnected-(IC6-DIO2-Pad18)") (class "Default")
      (node (ref "IC6") (pin "18") (pinfunction "DIO2_18") (pintype "bidirectional"))
    )
    (net (code "82") (name "unconnected-(IC6-DIO3-Pad17)") (class "Default")
      (node (ref "IC6") (pin "17") (pinfunction "DIO3_17") (pintype "bidirectional"))
    )
    (net (code "83") (name "unconnected-(IC6-DIO4-Pad11)") (class "Default")
      (node (ref "IC6") (pin "11") (pinfunction "DIO4_11") (pintype "bidirectional"))
    )
    (net (code "84") (name "unconnected-(IC6-DIO5-Pad15)") (class "Default")
      (node (ref "IC6") (pin "15") (pinfunction "DIO5_15") (pintype "bidirectional"))
    )
    (net (code "85") (name "unconnected-(IC6-DIO9-Pad13)") (class "Default")
      (node (ref "IC6") (pin "13") (pinfunction "DIO9_13") (pintype "bidirectional"))
    )
    (net (code "86") (name "unconnected-(IC6-DIO11-Pad7)") (class "Default")
      (node (ref "IC6") (pin "7") (pinfunction "DIO11_7") (pintype "bidirectional"))
    )
    (net (code "87") (name "unconnected-(IC6-DIO12-Pad4)") (class "Default")
      (node (ref "IC6") (pin "4") (pinfunction "DIO12_4") (pintype "bidirectional"))
    )
    (net (code "88") (name "unconnected-(IC6-RES-Pad8)") (class "Default")
      (node (ref "IC6") (pin "8") (pinfunction "RES_8") (pintype "bidirectional"))
    )
    (net (code "89") (name "unconnected-(IC6-RES-Pad14)") (class "Default")
      (node (ref "IC6") (pin "14") (pinfunction "RES_14") (pintype "bidirectional"))
    )
    (net (code "90") (name "unconnected-(IC7-PB6(OC1B{slash}OC4B{slash}ADC13)-Pad30)") (class "Default")
      (node (ref "IC7") (pin "30") (pinfunction "PB6(OC1B/OC4B/ADC13)_30") (pintype "bidirectional"))
    )
    (net (code "91") (name "unconnected-(IC7-PC6(OC3A{slash}~{OC4A})-Pad31)") (class "Default")
      (node (ref "IC7") (pin "31") (pinfunction "PC6(OC3A/~{OC4A})_31") (pintype "bidirectional"))
    )
    (net (code "92") (name "unconnected-(IC7-PC7(ICP3{slash}CLK0{slash}OC4A)-Pad32)") (class "Default")
      (node (ref "IC7") (pin "32") (pinfunction "PC7(ICP3/CLK0/OC4A)_32") (pintype "bidirectional"))
    )
    (net (code "93") (name "unconnected-(IC7-PE6(INT.6{slash}AIN0)-Pad1)") (class "Default")
      (node (ref "IC7") (pin "1") (pinfunction "PE6(INT.6/AIN0)_1") (pintype "bidirectional"))
    )
    (net (code "94") (name "unconnected-(IC7-PF0(ADC0)-Pad41)") (class "Default")
      (node (ref "IC7") (pin "41") (pinfunction "PF0(ADC0)_41") (pintype "bidirectional"))
    )
    (net (code "95") (name "unconnected-(IC7-PF1(ADC1)-Pad40)") (class "Default")
      (node (ref "IC7") (pin "40") (pinfunction "PF1(ADC1)_40") (pintype "bidirectional"))
    )
    (net (code "96") (name "unconnected-(IC7-PF4(ADC4{slash}TCK)-Pad39)") (class "Default")
      (node (ref "IC7") (pin "39") (pinfunction "PF4(ADC4/TCK)_39") (pintype "bidirectional"))
    )
    (net (code "97") (name "unconnected-(IC7-PF5(ADC5{slash}TMS)-Pad38)") (class "Default")
      (node (ref "IC7") (pin "38") (pinfunction "PF5(ADC5/TMS)_38") (pintype "bidirectional"))
    )
    (net (code "98") (name "unconnected-(IC7-PF6(ADC6{slash}TDO)-Pad37)") (class "Default")
      (node (ref "IC7") (pin "37") (pinfunction "PF6(ADC6/TDO)_37") (pintype "bidirectional"))
    )
    (net (code "99") (name "unconnected-(IC7-PF7(ADC7(TDI)-Pad36)") (class "Default")
      (node (ref "IC7") (pin "36") (pinfunction "PF7(ADC7(TDI)_36") (pintype "bidirectional"))
    )
    (net (code "100") (name "unconnected-(JK1-PadRSH)") (class "Default")
      (node (ref "JK1") (pin "RSH") (pinfunction "RSH_RSH") (pintype "bidirectional"))
    )
    (net (code "101") (name "unconnected-(JK2-PadRSH)") (class "Default")
      (node (ref "JK2") (pin "RSH") (pinfunction "RSH_RSH") (pintype "bidirectional"))
    )
    (net (code "102") (name "unconnected-(JK3-PadRSH)") (class "Default")
      (node (ref "JK3") (pin "RSH") (pinfunction "RSH_RSH") (pintype "bidirectional"))
    )
  )
)
